# esp8266_temp_monitor.net
KiCad netlist of a schematic drawn in EAGLE
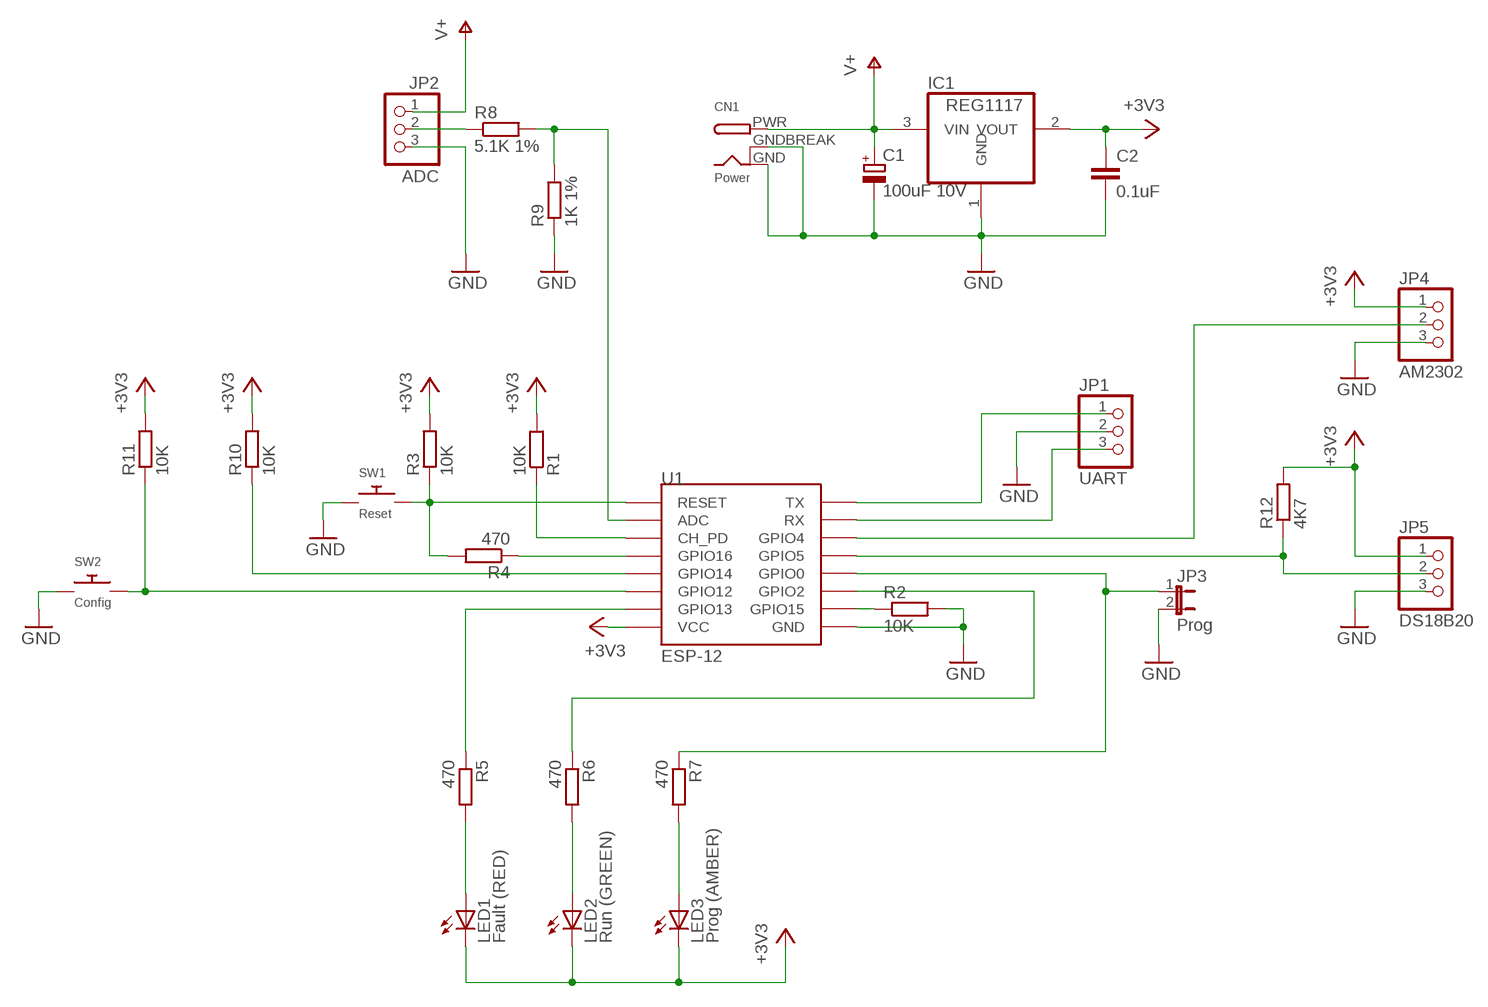
[diagram p0: schematic, sheet 1]

(export (version "E")
  (design (tool "Eeschema 10.0.6"))
  (components
    (comp (ref "C1")
      (value "100uF 10V")
      (footprint "eagle-import:E_7260-38W")
      (libsource (lib "eagle-import") (part "CPOL-EUE/7260-38W"))
    )
    (comp (ref "C2")
      (value "0.1uF")
      (footprint "eagle-import:C0805")
      (libsource (lib "eagle-import") (part "C-EUC0805"))
    )
    (comp (ref "CN1")
      (value "Power")
      (footprint "eagle-import:DCJACK_2MM_PTH")
      (libsource (lib "eagle-import") (part "DCBARRELPTH"))
    )
    (comp (ref "IC1")
      (value "REG1117")
      (footprint "eagle-import:SOT223")
      (libsource (lib "eagle-import") (part "REG1117"))
    )
    (comp (ref "JP1")
      (value "UART")
      (footprint "eagle-import:1X03")
      (libsource (lib "eagle-import") (part "PINHD-1X3"))
    )
    (comp (ref "JP2")
      (value "ADC")
      (footprint "eagle-import:1X03")
      (libsource (lib "eagle-import") (part "PINHD-1X3"))
    )
    (comp (ref "JP3")
      (value "Prog")
      (footprint "eagle-import:JP1")
      (libsource (lib "eagle-import") (part "JP1E"))
    )
    (comp (ref "JP4")
      (value "AM2302")
      (footprint "eagle-import:1X03")
      (libsource (lib "eagle-import") (part "PINHD-1X3"))
    )
    (comp (ref "JP5")
      (value "DS18B20")
      (footprint "eagle-import:1X03")
      (libsource (lib "eagle-import") (part "PINHD-1X3"))
    )
    (comp (ref "LED1")
      (value "Fault (RED)")
      (footprint "eagle-import:LED5MM")
      (libsource (lib "eagle-import") (part "LED5MM"))
    )
    (comp (ref "LED2")
      (value "Run (GREEN)")
      (footprint "eagle-import:LED5MM")
      (libsource (lib "eagle-import") (part "LED5MM"))
    )
    (comp (ref "LED3")
      (value "Prog (AMBER)")
      (footprint "eagle-import:LED5MM")
      (libsource (lib "eagle-import") (part "LED5MM"))
    )
    (comp (ref "R1")
      (value "10K")
      (footprint "eagle-import:R0805")
      (libsource (lib "eagle-import") (part "R-EU_R0805"))
    )
    (comp (ref "R2")
      (value "10K")
      (footprint "eagle-import:R0805")
      (libsource (lib "eagle-import") (part "R-EU_R0805"))
    )
    (comp (ref "R3")
      (value "10K")
      (footprint "eagle-import:M0805")
      (libsource (lib "eagle-import") (part "R-EU_M0805"))
    )
    (comp (ref "R4")
      (value "470")
      (footprint "eagle-import:M0805")
      (libsource (lib "eagle-import") (part "R-EU_M0805"))
    )
    (comp (ref "R5")
      (value "470")
      (footprint "eagle-import:M0805")
      (libsource (lib "eagle-import") (part "R-EU_M0805"))
    )
    (comp (ref "R6")
      (value "470")
      (footprint "eagle-import:M0805")
      (libsource (lib "eagle-import") (part "R-EU_M0805"))
    )
    (comp (ref "R7")
      (value "470")
      (footprint "eagle-import:M0805")
      (libsource (lib "eagle-import") (part "R-EU_M0805"))
    )
    (comp (ref "R8")
      (value "5.1K 1%")
      (footprint "eagle-import:M0805")
      (libsource (lib "eagle-import") (part "R-EU_M0805"))
    )
    (comp (ref "R9")
      (value "1K 1%")
      (footprint "eagle-import:M0805")
      (libsource (lib "eagle-import") (part "R-EU_M0805"))
    )
    (comp (ref "R10")
      (value "10K")
      (footprint "eagle-import:M0805")
      (libsource (lib "eagle-import") (part "R-EU_M0805"))
    )
    (comp (ref "R11")
      (value "10K")
      (footprint "eagle-import:M0805")
      (libsource (lib "eagle-import") (part "R-EU_M0805"))
    )
    (comp (ref "R12")
      (value "4K7")
      (footprint "eagle-import:M0805")
      (libsource (lib "eagle-import") (part "R-EU_M0805"))
    )
    (comp (ref "SW1")
      (value "Reset")
      (footprint "eagle-import:BTN_CK_KSS")
      (libsource (lib "eagle-import") (part "SWITCH_PUSHBUTTONC&K_KSS"))
    )
    (comp (ref "SW2")
      (value "Config")
      (footprint "eagle-import:BTN_CK_KSS")
      (libsource (lib "eagle-import") (part "SWITCH_PUSHBUTTONC&K_KSS"))
    )
    (comp (ref "U1")
      (value "ESP-12")
      (footprint "eagle-import:ESP12-SMD")
      (libsource (lib "eagle-import") (part "ESP12SMD"))
    )
  )
  (nets
    (net (code "1") (name "+3V3") (class "Default")
      (node (ref "C2") (pin "1") (pinfunction "1_1") (pintype "passive"))
      (node (ref "IC1") (pin "2") (pinfunction "VOUT_2") (pintype "power_in"))
      (node (ref "JP4") (pin "1") (pinfunction "1_1") (pintype "passive"))
      (node (ref "JP5") (pin "1") (pinfunction "1_1") (pintype "passive"))
      (node (ref "LED1") (pin "K") (pinfunction "C_K") (pintype "passive"))
      (node (ref "LED2") (pin "K") (pinfunction "C_K") (pintype "passive"))
      (node (ref "LED3") (pin "K") (pinfunction "C_K") (pintype "passive"))
      (node (ref "R1") (pin "2") (pinfunction "2_2") (pintype "passive"))
      (node (ref "R10") (pin "2") (pinfunction "2_2") (pintype "passive"))
      (node (ref "R11") (pin "2") (pinfunction "2_2") (pintype "passive"))
      (node (ref "R12") (pin "2") (pinfunction "2_2") (pintype "passive"))
      (node (ref "R3") (pin "2") (pinfunction "2_2") (pintype "passive"))
      (node (ref "U1") (pin "VCC") (pinfunction "VCC_VCC") (pintype "bidirectional"))
    )
    (net (code "2") (name "GND") (class "Default")
      (node (ref "C1") (pin "-") (pinfunction "-_-") (pintype "passive"))
      (node (ref "C2") (pin "2") (pinfunction "2_2") (pintype "passive"))
      (node (ref "CN1") (pin "GND") (pinfunction "GND_GND") (pintype "power_in"))
      (node (ref "CN1") (pin "GNDBREAK") (pinfunction "GNDBREAK_GNDBREAK") (pintype "power_in"))
      (node (ref "IC1") (pin "1") (pinfunction "GND_1") (pintype "power_in"))
      (node (ref "JP1") (pin "2") (pinfunction "2_2") (pintype "passive"))
      (node (ref "JP2") (pin "3") (pinfunction "3_3") (pintype "passive"))
      (node (ref "JP3") (pin "2") (pinfunction "2_2") (pintype "passive"))
      (node (ref "JP4") (pin "3") (pinfunction "3_3") (pintype "passive"))
      (node (ref "JP5") (pin "3") (pinfunction "3_3") (pintype "passive"))
      (node (ref "R2") (pin "2") (pinfunction "2_2") (pintype "passive"))
      (node (ref "R9") (pin "1") (pinfunction "1_1") (pintype "passive"))
      (node (ref "SW1") (pin "P$1") (pinfunction "P$1_P$1") (pintype "passive"))
      (node (ref "SW2") (pin "P$1") (pinfunction "P$1_P$1") (pintype "passive"))
      (node (ref "U1") (pin "GND") (pinfunction "GND_GND") (pintype "bidirectional"))
    )
    (net (code "3") (name "Net-(JP2-Pad2)") (class "Default")
      (node (ref "JP2") (pin "2") (pinfunction "2_2") (pintype "passive"))
      (node (ref "R8") (pin "1") (pinfunction "1_1") (pintype "passive"))
    )
    (net (code "4") (name "Net-(JP3-Pad1)") (class "Default")
      (node (ref "JP3") (pin "1") (pinfunction "1_1") (pintype "passive"))
      (node (ref "R7") (pin "1") (pinfunction "1_1") (pintype "passive"))
      (node (ref "U1") (pin "GPIO0") (pinfunction "GPIO0_GPIO0") (pintype "bidirectional"))
    )
    (net (code "5") (name "Net-(JP4-Pad2)") (class "Default")
      (node (ref "JP4") (pin "2") (pinfunction "2_2") (pintype "passive"))
      (node (ref "U1") (pin "GPIO4") (pinfunction "GPIO4_GPIO4") (pintype "bidirectional"))
    )
    (net (code "6") (name "Net-(JP5-Pad2)") (class "Default")
      (node (ref "JP5") (pin "2") (pinfunction "2_2") (pintype "passive"))
      (node (ref "R12") (pin "1") (pinfunction "1_1") (pintype "passive"))
      (node (ref "U1") (pin "GPIO5") (pinfunction "GPIO5_GPIO5") (pintype "bidirectional"))
    )
    (net (code "7") (name "Net-(LED1-PadA)") (class "Default")
      (node (ref "LED1") (pin "A") (pinfunction "A_A") (pintype "passive"))
      (node (ref "R5") (pin "2") (pinfunction "2_2") (pintype "passive"))
    )
    (net (code "8") (name "Net-(LED2-PadA)") (class "Default")
      (node (ref "LED2") (pin "A") (pinfunction "A_A") (pintype "passive"))
      (node (ref "R6") (pin "2") (pinfunction "2_2") (pintype "passive"))
    )
    (net (code "9") (name "Net-(LED3-PadA)") (class "Default")
      (node (ref "LED3") (pin "A") (pinfunction "A_A") (pintype "passive"))
      (node (ref "R7") (pin "2") (pinfunction "2_2") (pintype "passive"))
    )
    (net (code "10") (name "Net-(R1-Pad1)") (class "Default")
      (node (ref "R1") (pin "1") (pinfunction "1_1") (pintype "passive"))
      (node (ref "U1") (pin "CH_PD") (pinfunction "CH_PD_CH_PD") (pintype "bidirectional"))
    )
    (net (code "11") (name "Net-(R2-Pad1)") (class "Default")
      (node (ref "R2") (pin "1") (pinfunction "1_1") (pintype "passive"))
      (node (ref "U1") (pin "GPIO15") (pinfunction "GPIO15_GPIO15") (pintype "bidirectional"))
    )
    (net (code "12") (name "Net-(R3-Pad1)") (class "Default")
      (node (ref "R3") (pin "1") (pinfunction "1_1") (pintype "passive"))
      (node (ref "R4") (pin "2") (pinfunction "2_2") (pintype "passive"))
      (node (ref "SW1") (pin "P$2") (pinfunction "P$2_P$2") (pintype "passive"))
      (node (ref "U1") (pin "RESET") (pinfunction "RESET_RESET") (pintype "bidirectional"))
    )
    (net (code "13") (name "Net-(R4-Pad1)") (class "Default")
      (node (ref "R4") (pin "1") (pinfunction "1_1") (pintype "passive"))
      (node (ref "U1") (pin "GPIO16") (pinfunction "GPIO16_GPIO16") (pintype "bidirectional"))
    )
    (net (code "14") (name "Net-(R5-Pad1)") (class "Default")
      (node (ref "R5") (pin "1") (pinfunction "1_1") (pintype "passive"))
      (node (ref "U1") (pin "GPIO13") (pinfunction "GPIO13_GPIO13") (pintype "bidirectional"))
    )
    (net (code "15") (name "Net-(R6-Pad1)") (class "Default")
      (node (ref "R6") (pin "1") (pinfunction "1_1") (pintype "passive"))
      (node (ref "U1") (pin "GPIO2") (pinfunction "GPIO2_GPIO2") (pintype "bidirectional"))
    )
    (net (code "16") (name "Net-(R8-Pad2)") (class "Default")
      (node (ref "R8") (pin "2") (pinfunction "2_2") (pintype "passive"))
      (node (ref "R9") (pin "2") (pinfunction "2_2") (pintype "passive"))
      (node (ref "U1") (pin "ADC") (pinfunction "ADC_ADC") (pintype "bidirectional"))
    )
    (net (code "17") (name "Net-(R10-Pad1)") (class "Default")
      (node (ref "R10") (pin "1") (pinfunction "1_1") (pintype "passive"))
      (node (ref "U1") (pin "GPIO14") (pinfunction "GPIO14_GPIO14") (pintype "bidirectional"))
    )
    (net (code "18") (name "Net-(R11-Pad1)") (class "Default")
      (node (ref "R11") (pin "1") (pinfunction "1_1") (pintype "passive"))
      (node (ref "SW2") (pin "P$2") (pinfunction "P$2_P$2") (pintype "passive"))
      (node (ref "U1") (pin "GPIO12") (pinfunction "GPIO12_GPIO12") (pintype "bidirectional"))
    )
    (net (code "19") (name "Net-(U1-RX)") (class "Default")
      (node (ref "JP1") (pin "3") (pinfunction "3_3") (pintype "passive"))
      (node (ref "U1") (pin "RXD0") (pinfunction "RX_RXD0") (pintype "bidirectional"))
    )
    (net (code "20") (name "Net-(U1-TX)") (class "Default")
      (node (ref "JP1") (pin "1") (pinfunction "1_1") (pintype "passive"))
      (node (ref "U1") (pin "TXD0") (pinfunction "TX_TXD0") (pintype "bidirectional"))
    )
    (net (code "21") (name "V+") (class "Default")
      (node (ref "C1") (pin "+") (pinfunction "+_+") (pintype "passive"))
      (node (ref "CN1") (pin "PWR") (pinfunction "PWR_PWR") (pintype "power_in"))
      (node (ref "IC1") (pin "3") (pinfunction "VIN_3") (pintype "input"))
      (node (ref "JP2") (pin "1") (pinfunction "1_1") (pintype "passive"))
    )
  )
)
